# 7segement2digits1badidea-mk-1.net
KiCad netlist of a schematic drawn in EAGLE
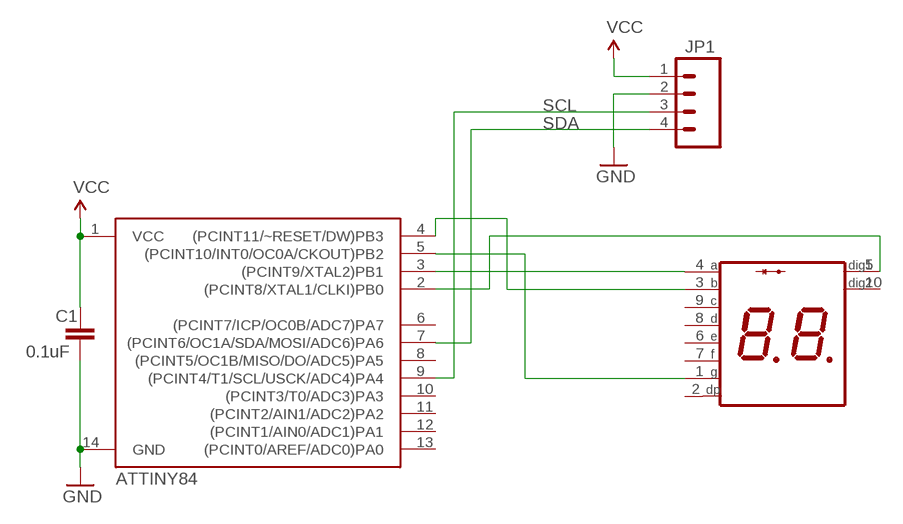
[diagram p0: schematic, sheet 1]

(export (version "E")
  (design (tool "Eeschema 10.0.6"))
  (components
    (comp (ref "C1")
      (value "0.1uF")
      (footprint "eagle-import:CAP-PTH-SMALL")
      (libsource (lib "eagle-import") (part "CAPPTH"))
    )
    (comp (ref "JP1")
      (value "M04PTH")
      (footprint "eagle-import:1X04")
      (libsource (lib "eagle-import") (part "M04PTH"))
    )
    (comp (ref "U$1")
      (value "7SEG_2DIG_CA")
      (footprint "eagle-import:7SEG_2DIG_FUCKYOU")
      (libsource (lib "eagle-import") (part "7SEG_2DIG_CA"))
    )
    (comp (ref "U$2")
      (value "ATTINY84")
      (footprint "eagle-import:SO14")
      (libsource (lib "eagle-import") (part "ATTINY84"))
    )
  )
  (nets
    (net (code "1") (name "/SCL") (class "Default")
      (node (ref "JP1") (pin "3") (pinfunction "3_3") (pintype "passive"))
      (node (ref "U$2") (pin "9") (pinfunction "(PCINT4/T1/SCL/USCK/ADC4)PA4_9") (pintype "bidirectional"))
    )
    (net (code "2") (name "/SDA") (class "Default")
      (node (ref "JP1") (pin "4") (pinfunction "4_4") (pintype "passive"))
      (node (ref "U$2") (pin "7") (pinfunction "(PCINT6/OC1A/SDA/MOSI/ADC6)PA6_7") (pintype "bidirectional"))
    )
    (net (code "3") (name "GND") (class "Default")
      (node (ref "C1") (pin "2") (pinfunction "2_2") (pintype "passive"))
      (node (ref "JP1") (pin "2") (pinfunction "2_2") (pintype "passive"))
      (node (ref "U$2") (pin "14") (pinfunction "GND_14") (pintype "bidirectional"))
    )
    (net (code "4") (name "Net-(U$1-A)") (class "Default")
      (node (ref "U$1") (pin "4") (pinfunction "A_4") (pintype "passive"))
      (node (ref "U$2") (pin "3") (pinfunction "(PCINT9/XTAL2)PB1_3") (pintype "bidirectional"))
    )
    (net (code "5") (name "Net-(U$1-B)") (class "Default")
      (node (ref "U$1") (pin "3") (pinfunction "B_3") (pintype "passive"))
      (node (ref "U$2") (pin "4") (pinfunction "(PCINT11/~{RESET/DW})PB3_4") (pintype "bidirectional"))
    )
    (net (code "6") (name "Net-(U$1-DIG1)") (class "Default")
      (node (ref "U$1") (pin "5") (pinfunction "DIG1_5") (pintype "passive"))
      (node (ref "U$2") (pin "2") (pinfunction "(PCINT8/XTAL1/CLKI)PB0_2") (pintype "bidirectional"))
    )
    (net (code "7") (name "Net-(U$1-G)") (class "Default")
      (node (ref "U$1") (pin "1") (pinfunction "G_1") (pintype "passive"))
      (node (ref "U$2") (pin "5") (pinfunction "(PCINT10/INT0/OC0A/CKOUT)PB2_5") (pintype "bidirectional"))
    )
    (net (code "8") (name "VCC") (class "Default")
      (node (ref "C1") (pin "1") (pinfunction "1_1") (pintype "passive"))
      (node (ref "JP1") (pin "1") (pinfunction "1_1") (pintype "passive"))
      (node (ref "U$2") (pin "1") (pinfunction "VCC_1") (pintype "bidirectional"))
    )
    (net (code "9") (name "unconnected-(U$1-C-Pad9)") (class "Default")
      (node (ref "U$1") (pin "9") (pinfunction "C_9") (pintype "passive"))
    )
    (net (code "10") (name "unconnected-(U$1-D-Pad8)") (class "Default")
      (node (ref "U$1") (pin "8") (pinfunction "D_8") (pintype "passive"))
    )
    (net (code "11") (name "unconnected-(U$1-DIG2-Pad10)") (class "Default")
      (node (ref "U$1") (pin "10") (pinfunction "DIG2_10") (pintype "passive"))
    )
    (net (code "12") (name "unconnected-(U$1-DP-Pad2)") (class "Default")
      (node (ref "U$1") (pin "2") (pinfunction "DP_2") (pintype "passive"))
    )
    (net (code "13") (name "unconnected-(U$1-E-Pad6)") (class "Default")
      (node (ref "U$1") (pin "6") (pinfunction "E_6") (pintype "passive"))
    )
    (net (code "14") (name "unconnected-(U$1-F-Pad7)") (class "Default")
      (node (ref "U$1") (pin "7") (pinfunction "F_7") (pintype "passive"))
    )
    (net (code "15") (name "unconnected-(U$2-(PCINT0{slash}AREF{slash}ADC0)PA0-Pad13)") (class "Default")
      (node (ref "U$2") (pin "13") (pinfunction "(PCINT0/AREF/ADC0)PA0_13") (pintype "bidirectional"))
    )
    (net (code "16") (name "unconnected-(U$2-(PCINT1{slash}AIN0{slash}ADC1)PA1-Pad12)") (class "Default")
      (node (ref "U$2") (pin "12") (pinfunction "(PCINT1/AIN0/ADC1)PA1_12") (pintype "bidirectional"))
    )
    (net (code "17") (name "unconnected-(U$2-(PCINT2{slash}AIN1{slash}ADC2)PA2-Pad11)") (class "Default")
      (node (ref "U$2") (pin "11") (pinfunction "(PCINT2/AIN1/ADC2)PA2_11") (pintype "bidirectional"))
    )
    (net (code "18") (name "unconnected-(U$2-(PCINT3{slash}T0{slash}ADC3)PA3-Pad10)") (class "Default")
      (node (ref "U$2") (pin "10") (pinfunction "(PCINT3/T0/ADC3)PA3_10") (pintype "bidirectional"))
    )
    (net (code "19") (name "unconnected-(U$2-(PCINT5{slash}OC1B{slash}MISO{slash}DO{slash}ADC5)PA5-Pad8)") (class "Default")
      (node (ref "U$2") (pin "8") (pinfunction "(PCINT5/OC1B/MISO/DO/ADC5)PA5_8") (pintype "bidirectional"))
    )
    (net (code "20") (name "unconnected-(U$2-(PCINT7{slash}ICP{slash}OC0B{slash}ADC7)PA7-Pad6)") (class "Default")
      (node (ref "U$2") (pin "6") (pinfunction "(PCINT7/ICP/OC0B/ADC7)PA7_6") (pintype "bidirectional"))
    )
  )
)
